# rc-driver.net
KiCad netlist of a schematic drawn in EAGLE
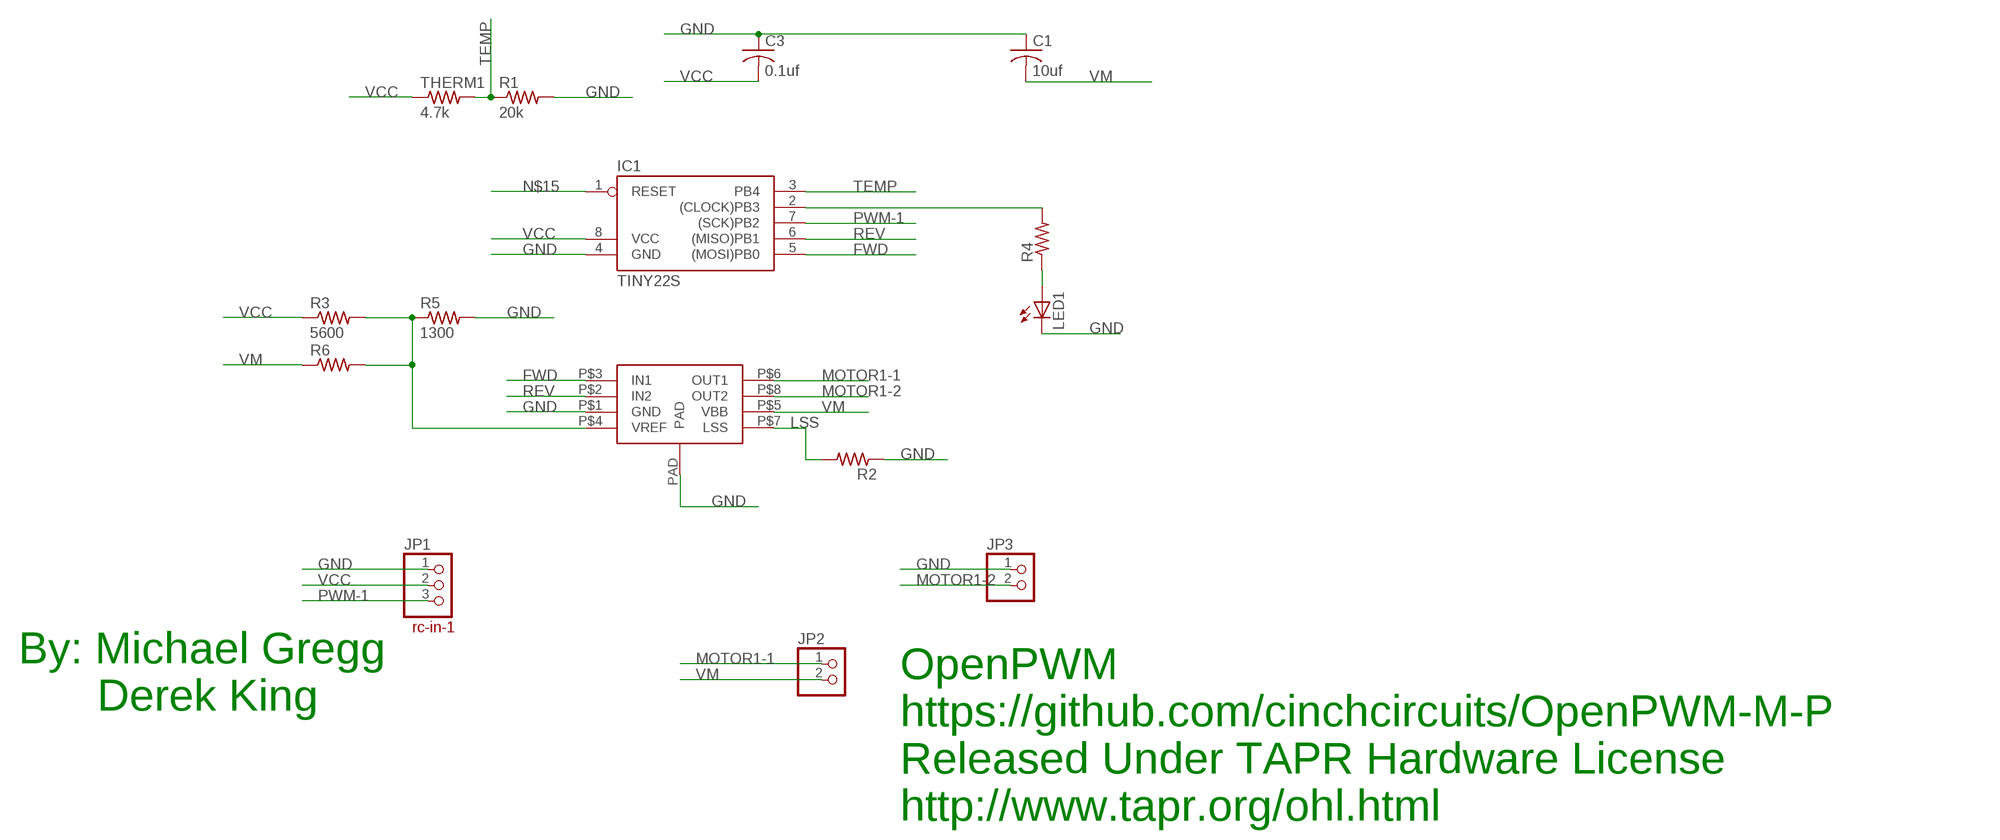
[diagram p0: schematic, sheet 1]

(export (version "E")
  (design (tool "Eeschema 10.0.6"))
  (components
    (comp (ref "C1")
      (value "10uf")
      (footprint "eagle-import:C1210")
      (libsource (lib "eagle-import") (part "C-USC1210"))
    )
    (comp (ref "C3")
      (value "0.1uf")
      (footprint "eagle-import:C0805")
      (libsource (lib "eagle-import") (part "C-USC0805"))
    )
    (comp (ref "IC1")
      (value "TINY22S")
      (footprint "eagle-import:SOIC8")
      (libsource (lib "eagle-import") (part "TINY22S"))
    )
    (comp (ref "JP1")
      (value "PINHD-1X3")
      (footprint "eagle-import:1X03")
      (libsource (lib "eagle-import") (part "PINHD-1X3"))
    )
    (comp (ref "JP2")
      (value "PINHD-1X2")
      (footprint "eagle-import:1X02")
      (libsource (lib "eagle-import") (part "PINHD-1X2"))
    )
    (comp (ref "JP3")
      (value "PINHD-1X2")
      (footprint "eagle-import:1X02")
      (libsource (lib "eagle-import") (part "PINHD-1X2"))
    )
    (comp (ref "LED1")
      (value "LEDCHIP-LED0603")
      (footprint "eagle-import:CHIP-LED0603")
      (libsource (lib "eagle-import") (part "LEDCHIP-LED0603"))
    )
    (comp (ref "R1")
      (value "20k")
      (footprint "eagle-import:R0603")
      (libsource (lib "eagle-import") (part "R-US_R0603"))
    )
    (comp (ref "R2")
      (value "R-US_R0805W")
      (footprint "eagle-import:R0805W")
      (libsource (lib "eagle-import") (part "R-US_R0805W"))
    )
    (comp (ref "R3")
      (value "5600")
      (footprint "eagle-import:R0603")
      (libsource (lib "eagle-import") (part "R-US_R0603"))
    )
    (comp (ref "R4")
      (value "R-US_R0603")
      (footprint "eagle-import:R0603")
      (libsource (lib "eagle-import") (part "R-US_R0603"))
    )
    (comp (ref "R5")
      (value "1300")
      (footprint "eagle-import:R0603")
      (libsource (lib "eagle-import") (part "R-US_R0603"))
    )
    (comp (ref "R6")
      (value "R-US_R0603")
      (footprint "eagle-import:R0603")
      (libsource (lib "eagle-import") (part "R-US_R0603"))
    )
    (comp (ref "THERM1")
      (value "4.7k")
      (footprint "eagle-import:R0603")
      (libsource (lib "eagle-import") (part "R-US_R0603"))
    )
    (comp (ref "U$1")
      (value "A4950-HBRIDGE")
      (footprint "eagle-import:SO-8EP")
      (libsource (lib "eagle-import") (part "A4950-HBRIDGE"))
    )
  )
  (nets
    (net (code "1") (name "/FWD") (class "Default")
      (node (ref "IC1") (pin "5") (pinfunction "(MOSI)PB0_5") (pintype "bidirectional"))
      (node (ref "U$1") (pin "P$3") (pinfunction "IN1_P$3") (pintype "bidirectional"))
    )
    (net (code "2") (name "/GND") (class "Default")
      (node (ref "C1") (pin "1") (pinfunction "1_1") (pintype "passive"))
      (node (ref "C3") (pin "1") (pinfunction "1_1") (pintype "passive"))
      (node (ref "IC1") (pin "4") (pinfunction "GND_4") (pintype "power_in"))
      (node (ref "JP1") (pin "1") (pinfunction "1_1") (pintype "passive"))
      (node (ref "JP3") (pin "1") (pinfunction "1_1") (pintype "passive"))
      (node (ref "LED1") (pin "C") (pinfunction "C_C") (pintype "passive"))
      (node (ref "R1") (pin "2") (pinfunction "2_2") (pintype "passive"))
      (node (ref "R2") (pin "1") (pinfunction "1_1") (pintype "passive"))
      (node (ref "R5") (pin "2") (pinfunction "2_2") (pintype "passive"))
      (node (ref "U$1") (pin "P$1") (pinfunction "GND_P$1") (pintype "bidirectional"))
      (node (ref "U$1") (pin "PAD") (pinfunction "PAD_PAD") (pintype "bidirectional"))
    )
    (net (code "3") (name "/LSS") (class "Default")
      (node (ref "R2") (pin "2") (pinfunction "2_2") (pintype "passive"))
      (node (ref "U$1") (pin "P$7") (pinfunction "LSS_P$7") (pintype "bidirectional"))
    )
    (net (code "4") (name "/MOTOR1-1") (class "Default")
      (node (ref "JP2") (pin "1") (pinfunction "1_1") (pintype "passive"))
      (node (ref "U$1") (pin "P$6") (pinfunction "OUT1_P$6") (pintype "bidirectional"))
    )
    (net (code "5") (name "/MOTOR1-2") (class "Default")
      (node (ref "JP3") (pin "2") (pinfunction "2_2") (pintype "passive"))
      (node (ref "U$1") (pin "P$8") (pinfunction "OUT2_P$8") (pintype "bidirectional"))
    )
    (net (code "6") (name "/N$15") (class "Default")
      (node (ref "IC1") (pin "1") (pinfunction "RESET_1") (pintype "input"))
    )
    (net (code "7") (name "/PWM-1") (class "Default")
      (node (ref "IC1") (pin "7") (pinfunction "(SCK)PB2_7") (pintype "bidirectional"))
      (node (ref "JP1") (pin "3") (pinfunction "3_3") (pintype "passive"))
    )
    (net (code "8") (name "/REV") (class "Default")
      (node (ref "IC1") (pin "6") (pinfunction "(MISO)PB1_6") (pintype "bidirectional"))
      (node (ref "U$1") (pin "P$2") (pinfunction "IN2_P$2") (pintype "bidirectional"))
    )
    (net (code "9") (name "/TEMP") (class "Default")
      (node (ref "IC1") (pin "3") (pinfunction "PB4_3") (pintype "bidirectional"))
      (node (ref "R1") (pin "1") (pinfunction "1_1") (pintype "passive"))
      (node (ref "THERM1") (pin "2") (pinfunction "2_2") (pintype "passive"))
    )
    (net (code "10") (name "/VCC") (class "Default")
      (node (ref "C3") (pin "2") (pinfunction "2_2") (pintype "passive"))
      (node (ref "IC1") (pin "8") (pinfunction "VCC_8") (pintype "power_in"))
      (node (ref "JP1") (pin "2") (pinfunction "2_2") (pintype "passive"))
      (node (ref "R3") (pin "1") (pinfunction "1_1") (pintype "passive"))
      (node (ref "THERM1") (pin "1") (pinfunction "1_1") (pintype "passive"))
    )
    (net (code "11") (name "/VM") (class "Default")
      (node (ref "C1") (pin "2") (pinfunction "2_2") (pintype "passive"))
      (node (ref "JP2") (pin "2") (pinfunction "2_2") (pintype "passive"))
      (node (ref "R6") (pin "1") (pinfunction "1_1") (pintype "passive"))
      (node (ref "U$1") (pin "P$5") (pinfunction "VBB_P$5") (pintype "bidirectional"))
    )
    (net (code "12") (name "Net-(IC1-(CLOCK)PB3)") (class "Default")
      (node (ref "IC1") (pin "2") (pinfunction "(CLOCK)PB3_2") (pintype "bidirectional"))
      (node (ref "R4") (pin "2") (pinfunction "2_2") (pintype "passive"))
    )
    (net (code "13") (name "Net-(LED1-PadA)") (class "Default")
      (node (ref "LED1") (pin "A") (pinfunction "A_A") (pintype "passive"))
      (node (ref "R4") (pin "1") (pinfunction "1_1") (pintype "passive"))
    )
    (net (code "14") (name "Net-(U$1-VREF)") (class "Default")
      (node (ref "R3") (pin "2") (pinfunction "2_2") (pintype "passive"))
      (node (ref "R5") (pin "1") (pinfunction "1_1") (pintype "passive"))
      (node (ref "R6") (pin "2") (pinfunction "2_2") (pintype "passive"))
      (node (ref "U$1") (pin "P$4") (pinfunction "VREF_P$4") (pintype "bidirectional"))
    )
  )
)
